# ASD2831.net
KiCad netlist of a schematic drawn in EAGLE
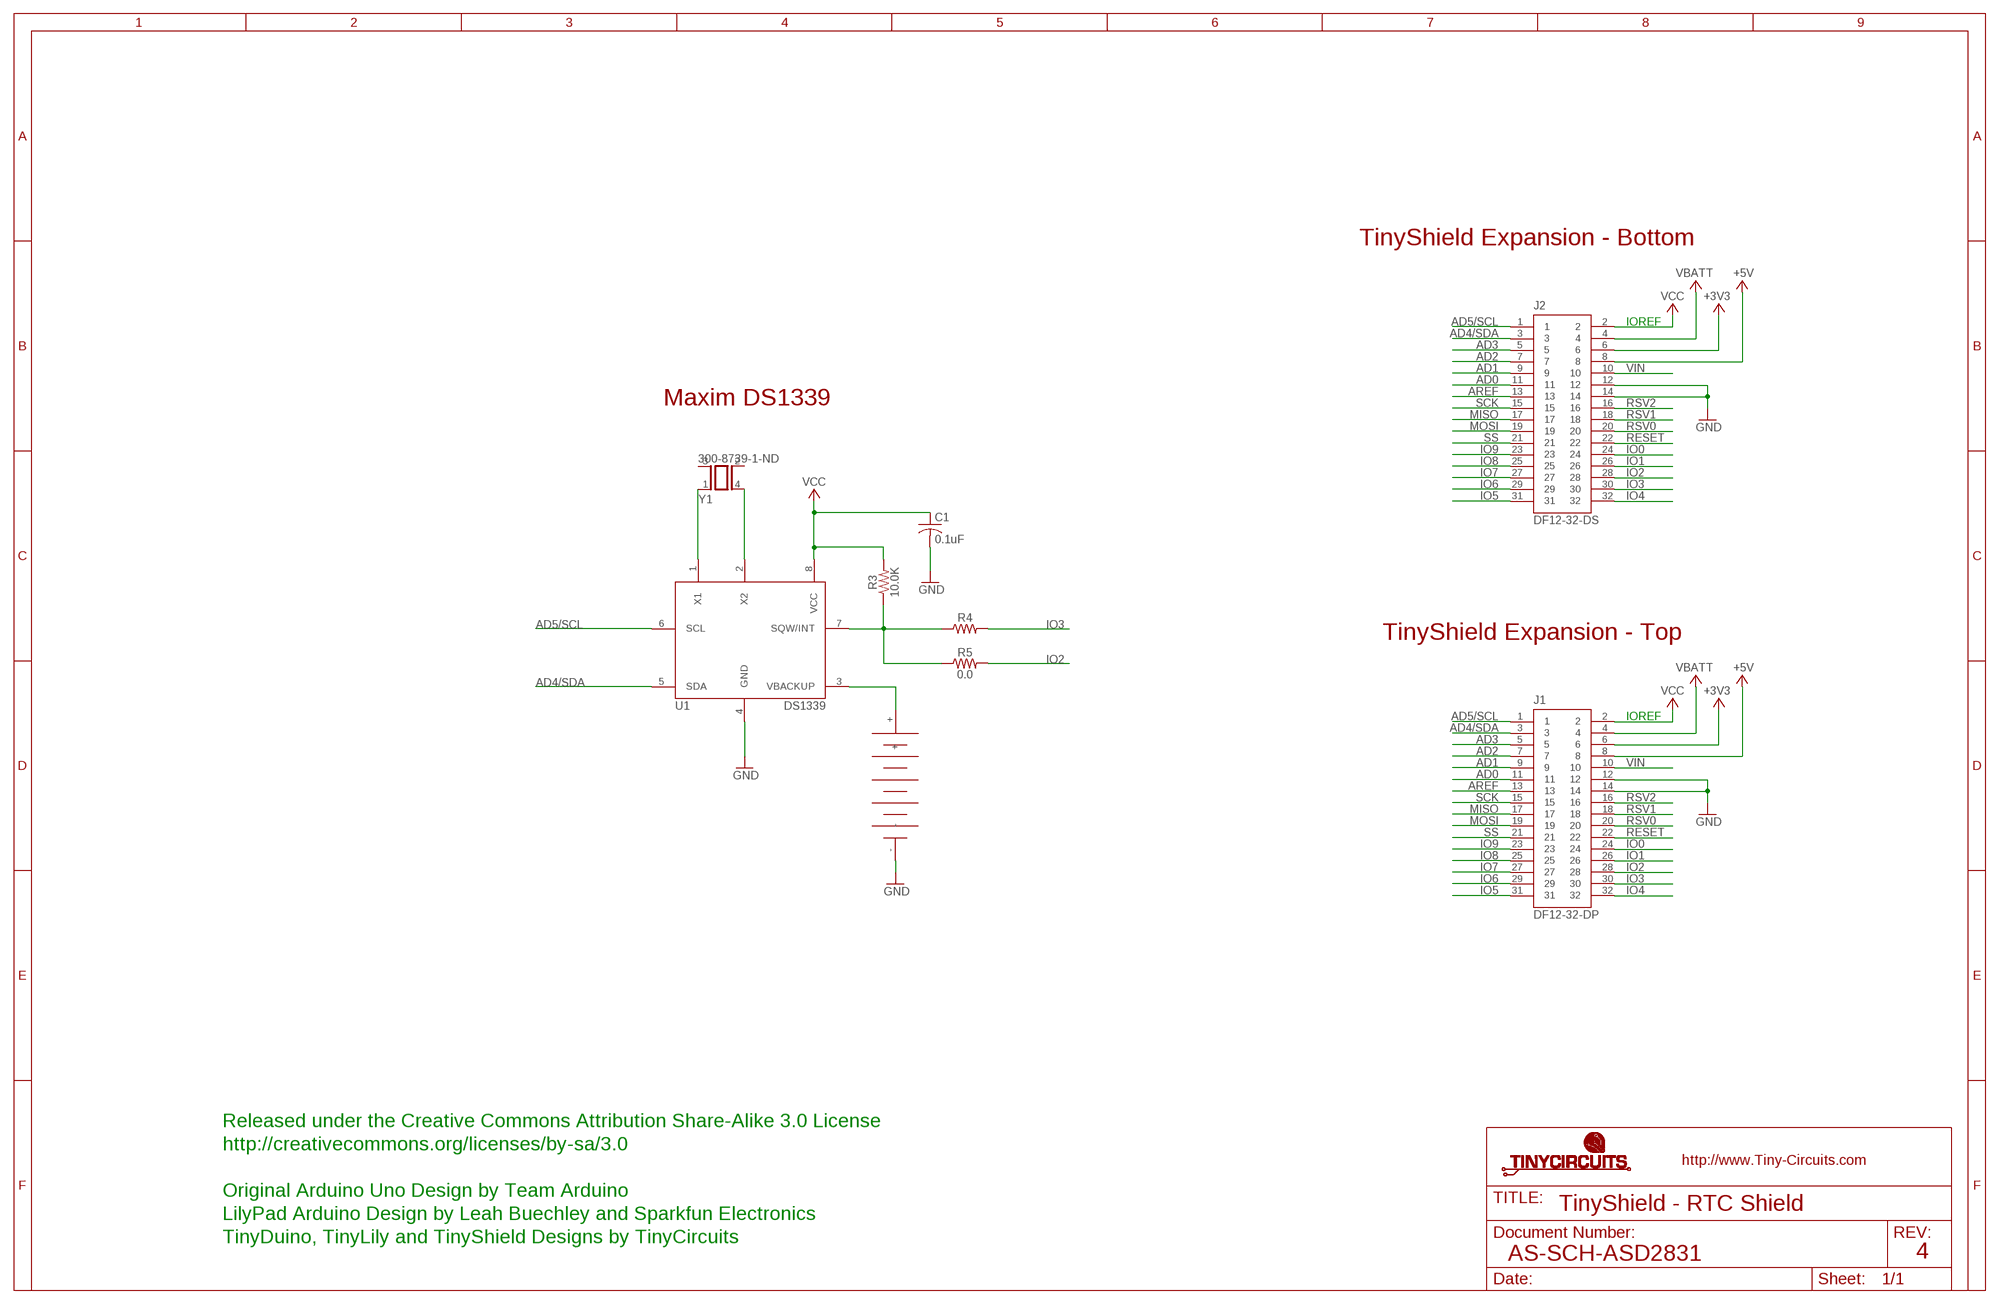
[diagram p0: schematic, sheet 1]

(export (version "E")
  (design (tool "Eeschema 10.0.6"))
  (components
    (comp (ref "B1")
      (value "ML-920S/DN")
      (footprint "eagle-import:ML-920S_DN")
      (fields (field (name "PARTNO") "AS-ITM-00182"))
      (libsource (lib "eagle-import") (part "AS-ITM-00182"))
    )
    (comp (ref "C1")
      (value "0.1uF")
      (footprint "eagle-import:C0402")
      (fields (field (name "PARTNO") "AS-ITM-00008"))
      (libsource (lib "eagle-import") (part "AS-ITM-00008"))
    )
    (comp (ref "J1")
      (value "DF12-32-DP")
      (footprint "eagle-import:DF12-32-DP")
      (fields (field (name "PARTNO") "AS-ITM-00015") (field (name "PARTNO_1") "AS-ITM-00015"))
      (libsource (lib "eagle-import") (part "AS-ITM-00015"))
    )
    (comp (ref "J2")
      (value "DF12-32-DS")
      (footprint "eagle-import:DF12-32-DS")
      (fields (field (name "PARTNO") "AS-ITM-00012") (field (name "PARTNO_1") "AS-ITM-00012"))
      (libsource (lib "eagle-import") (part "AS-ITM-00012"))
    )
    (comp (ref "R3")
      (value "10.0K")
      (footprint "eagle-import:0402")
      (fields (field (name "PARTNO") "AS-ITM-00032") (field (name "PARTNO_1") "AS-ITM-00032"))
      (libsource (lib "eagle-import") (part "AS-ITM-00032"))
    )
    (comp (ref "R4")
      (value "AS-ITM-000760402_SHORT")
      (footprint "eagle-import:0402_SHORT")
      (libsource (lib "eagle-import") (part "AS-ITM-000760402_SHORT"))
    )
    (comp (ref "R5")
      (value "0.0")
      (footprint "eagle-import:0402")
      (fields (field (name "PARTNO") "AS-ITM-00076"))
      (libsource (lib "eagle-import") (part "AS-ITM-00076"))
    )
    (comp (ref "U1")
      (value "DS1339")
      (footprint "eagle-import:8-USOP")
      (fields (field (name "PARTNO") "AS-ITM-00181"))
      (libsource (lib "eagle-import") (part "AS-ITM-00181"))
    )
    (comp (ref "Y1")
      (value "300-8739-1-ND")
      (footprint "eagle-import:CM200C-32.768KDZBT")
      (fields (field (name "PARTNO") "AS-ITM-00183"))
      (libsource (lib "eagle-import") (part "AS-ITM-00183"))
    )
  )
  (nets
    (net (code "1") (name "+3V3") (class "Default")
      (node (ref "J1") (pin "6") (pinfunction "6_6") (pintype "bidirectional"))
      (node (ref "J2") (pin "6") (pinfunction "6_6") (pintype "bidirectional"))
    )
    (net (code "2") (name "+5V") (class "Default")
      (node (ref "J1") (pin "8") (pinfunction "8_8") (pintype "bidirectional"))
      (node (ref "J2") (pin "8") (pinfunction "8_8") (pintype "bidirectional"))
    )
    (net (code "3") (name "/AD0") (class "Default")
      (node (ref "J1") (pin "11") (pinfunction "11_11") (pintype "bidirectional"))
      (node (ref "J2") (pin "11") (pinfunction "11_11") (pintype "bidirectional"))
    )
    (net (code "4") (name "/AD1") (class "Default")
      (node (ref "J1") (pin "9") (pinfunction "9_9") (pintype "bidirectional"))
      (node (ref "J2") (pin "9") (pinfunction "9_9") (pintype "bidirectional"))
    )
    (net (code "5") (name "/AD2") (class "Default")
      (node (ref "J1") (pin "7") (pinfunction "7_7") (pintype "bidirectional"))
      (node (ref "J2") (pin "7") (pinfunction "7_7") (pintype "bidirectional"))
    )
    (net (code "6") (name "/AD3") (class "Default")
      (node (ref "J1") (pin "5") (pinfunction "5_5") (pintype "bidirectional"))
      (node (ref "J2") (pin "5") (pinfunction "5_5") (pintype "bidirectional"))
    )
    (net (code "7") (name "/AD4{slash}SDA") (class "Default")
      (node (ref "J1") (pin "3") (pinfunction "3_3") (pintype "bidirectional"))
      (node (ref "J2") (pin "3") (pinfunction "3_3") (pintype "bidirectional"))
      (node (ref "U1") (pin "5") (pinfunction "SDA_5") (pintype "bidirectional"))
    )
    (net (code "8") (name "/AD5{slash}SCL") (class "Default")
      (node (ref "J1") (pin "1") (pinfunction "1_1") (pintype "bidirectional"))
      (node (ref "J2") (pin "1") (pinfunction "1_1") (pintype "bidirectional"))
      (node (ref "U1") (pin "6") (pinfunction "SCL_6") (pintype "bidirectional"))
    )
    (net (code "9") (name "/AREF") (class "Default")
      (node (ref "J1") (pin "13") (pinfunction "13_13") (pintype "bidirectional"))
      (node (ref "J2") (pin "13") (pinfunction "13_13") (pintype "bidirectional"))
    )
    (net (code "10") (name "/IO0") (class "Default")
      (node (ref "J1") (pin "24") (pinfunction "24_24") (pintype "bidirectional"))
      (node (ref "J2") (pin "24") (pinfunction "24_24") (pintype "bidirectional"))
    )
    (net (code "11") (name "/IO1") (class "Default")
      (node (ref "J1") (pin "26") (pinfunction "26_26") (pintype "bidirectional"))
      (node (ref "J2") (pin "26") (pinfunction "26_26") (pintype "bidirectional"))
    )
    (net (code "12") (name "/IO2") (class "Default")
      (node (ref "J1") (pin "28") (pinfunction "28_28") (pintype "bidirectional"))
      (node (ref "J2") (pin "28") (pinfunction "28_28") (pintype "bidirectional"))
      (node (ref "R5") (pin "2") (pinfunction "2_2") (pintype "passive"))
    )
    (net (code "13") (name "/IO3") (class "Default")
      (node (ref "J1") (pin "30") (pinfunction "30_30") (pintype "bidirectional"))
      (node (ref "J2") (pin "30") (pinfunction "30_30") (pintype "bidirectional"))
      (node (ref "R4") (pin "2") (pinfunction "2_2") (pintype "passive"))
    )
    (net (code "14") (name "/IO4") (class "Default")
      (node (ref "J1") (pin "32") (pinfunction "32_32") (pintype "bidirectional"))
      (node (ref "J2") (pin "32") (pinfunction "32_32") (pintype "bidirectional"))
    )
    (net (code "15") (name "/IO5") (class "Default")
      (node (ref "J1") (pin "31") (pinfunction "31_31") (pintype "bidirectional"))
      (node (ref "J2") (pin "31") (pinfunction "31_31") (pintype "bidirectional"))
    )
    (net (code "16") (name "/IO6") (class "Default")
      (node (ref "J1") (pin "29") (pinfunction "29_29") (pintype "bidirectional"))
      (node (ref "J2") (pin "29") (pinfunction "29_29") (pintype "bidirectional"))
    )
    (net (code "17") (name "/IO7") (class "Default")
      (node (ref "J1") (pin "27") (pinfunction "27_27") (pintype "bidirectional"))
      (node (ref "J2") (pin "27") (pinfunction "27_27") (pintype "bidirectional"))
    )
    (net (code "18") (name "/IO8") (class "Default")
      (node (ref "J1") (pin "25") (pinfunction "25_25") (pintype "bidirectional"))
      (node (ref "J2") (pin "25") (pinfunction "25_25") (pintype "bidirectional"))
    )
    (net (code "19") (name "/IO9") (class "Default")
      (node (ref "J1") (pin "23") (pinfunction "23_23") (pintype "bidirectional"))
      (node (ref "J2") (pin "23") (pinfunction "23_23") (pintype "bidirectional"))
    )
    (net (code "20") (name "/MISO") (class "Default")
      (node (ref "J1") (pin "17") (pinfunction "17_17") (pintype "bidirectional"))
      (node (ref "J2") (pin "17") (pinfunction "17_17") (pintype "bidirectional"))
    )
    (net (code "21") (name "/MOSI") (class "Default")
      (node (ref "J1") (pin "19") (pinfunction "19_19") (pintype "bidirectional"))
      (node (ref "J2") (pin "19") (pinfunction "19_19") (pintype "bidirectional"))
    )
    (net (code "22") (name "/RESET") (class "Default")
      (node (ref "J1") (pin "22") (pinfunction "22_22") (pintype "bidirectional"))
      (node (ref "J2") (pin "22") (pinfunction "22_22") (pintype "bidirectional"))
    )
    (net (code "23") (name "/RSV0") (class "Default")
      (node (ref "J1") (pin "20") (pinfunction "20_20") (pintype "bidirectional"))
      (node (ref "J2") (pin "20") (pinfunction "20_20") (pintype "bidirectional"))
    )
    (net (code "24") (name "/RSV1") (class "Default")
      (node (ref "J1") (pin "18") (pinfunction "18_18") (pintype "bidirectional"))
      (node (ref "J2") (pin "18") (pinfunction "18_18") (pintype "bidirectional"))
    )
    (net (code "25") (name "/RSV2") (class "Default")
      (node (ref "J1") (pin "16") (pinfunction "16_16") (pintype "bidirectional"))
      (node (ref "J2") (pin "16") (pinfunction "16_16") (pintype "bidirectional"))
    )
    (net (code "26") (name "/SCK") (class "Default")
      (node (ref "J1") (pin "15") (pinfunction "15_15") (pintype "bidirectional"))
      (node (ref "J2") (pin "15") (pinfunction "15_15") (pintype "bidirectional"))
    )
    (net (code "27") (name "/SS") (class "Default")
      (node (ref "J1") (pin "21") (pinfunction "21_21") (pintype "bidirectional"))
      (node (ref "J2") (pin "21") (pinfunction "21_21") (pintype "bidirectional"))
    )
    (net (code "28") (name "/VIN") (class "Default")
      (node (ref "J1") (pin "10") (pinfunction "10_10") (pintype "bidirectional"))
      (node (ref "J2") (pin "10") (pinfunction "10_10") (pintype "bidirectional"))
    )
    (net (code "29") (name "GND") (class "Default")
      (node (ref "B1") (pin "-") (pinfunction "-_-") (pintype "bidirectional"))
      (node (ref "C1") (pin "2") (pinfunction "2_2") (pintype "passive"))
      (node (ref "J1") (pin "12") (pinfunction "12_12") (pintype "bidirectional"))
      (node (ref "J1") (pin "14") (pinfunction "14_14") (pintype "bidirectional"))
      (node (ref "J2") (pin "12") (pinfunction "12_12") (pintype "bidirectional"))
      (node (ref "J2") (pin "14") (pinfunction "14_14") (pintype "bidirectional"))
      (node (ref "U1") (pin "4") (pinfunction "GND_4") (pintype "bidirectional"))
    )
    (net (code "30") (name "Net-(U1-SQW{slash}INT)") (class "Default")
      (node (ref "R3") (pin "1") (pinfunction "1_1") (pintype "passive"))
      (node (ref "R4") (pin "1") (pinfunction "1_1") (pintype "passive"))
      (node (ref "R5") (pin "1") (pinfunction "1_1") (pintype "passive"))
      (node (ref "U1") (pin "7") (pinfunction "SQW/INT_7") (pintype "bidirectional"))
    )
    (net (code "31") (name "Net-(U1-VBACKUP)") (class "Default")
      (node (ref "B1") (pin "+") (pinfunction "+_+") (pintype "bidirectional"))
      (node (ref "U1") (pin "3") (pinfunction "VBACKUP_3") (pintype "bidirectional"))
    )
    (net (code "32") (name "Net-(U1-X1)") (class "Default")
      (node (ref "U1") (pin "1") (pinfunction "X1_1") (pintype "bidirectional"))
      (node (ref "Y1") (pin "1") (pinfunction "1_1") (pintype "passive"))
    )
    (net (code "33") (name "Net-(U1-X2)") (class "Default")
      (node (ref "U1") (pin "2") (pinfunction "X2_2") (pintype "bidirectional"))
      (node (ref "Y1") (pin "4") (pinfunction "2_4") (pintype "passive"))
    )
    (net (code "34") (name "VBATT") (class "Default")
      (node (ref "J1") (pin "4") (pinfunction "4_4") (pintype "bidirectional"))
      (node (ref "J2") (pin "4") (pinfunction "4_4") (pintype "bidirectional"))
    )
    (net (code "35") (name "VCC") (class "Default")
      (node (ref "C1") (pin "1") (pinfunction "1_1") (pintype "passive"))
      (node (ref "J1") (pin "2") (pinfunction "2_2") (pintype "bidirectional"))
      (node (ref "J2") (pin "2") (pinfunction "2_2") (pintype "bidirectional"))
      (node (ref "R3") (pin "2") (pinfunction "2_2") (pintype "passive"))
      (node (ref "U1") (pin "8") (pinfunction "VCC_8") (pintype "bidirectional"))
    )
    (net (code "36") (name "unconnected-(Y1-3-Pad2)") (class "Default")
      (node (ref "Y1") (pin "2") (pinfunction "3_2") (pintype "passive"))
    )
    (net (code "37") (name "unconnected-(Y1-4-Pad3)") (class "Default")
      (node (ref "Y1") (pin "3") (pinfunction "4_3") (pintype "passive"))
    )
  )
)
